# DCMotorCTRL.net
KiCad netlist of a schematic drawn in Altium Designer
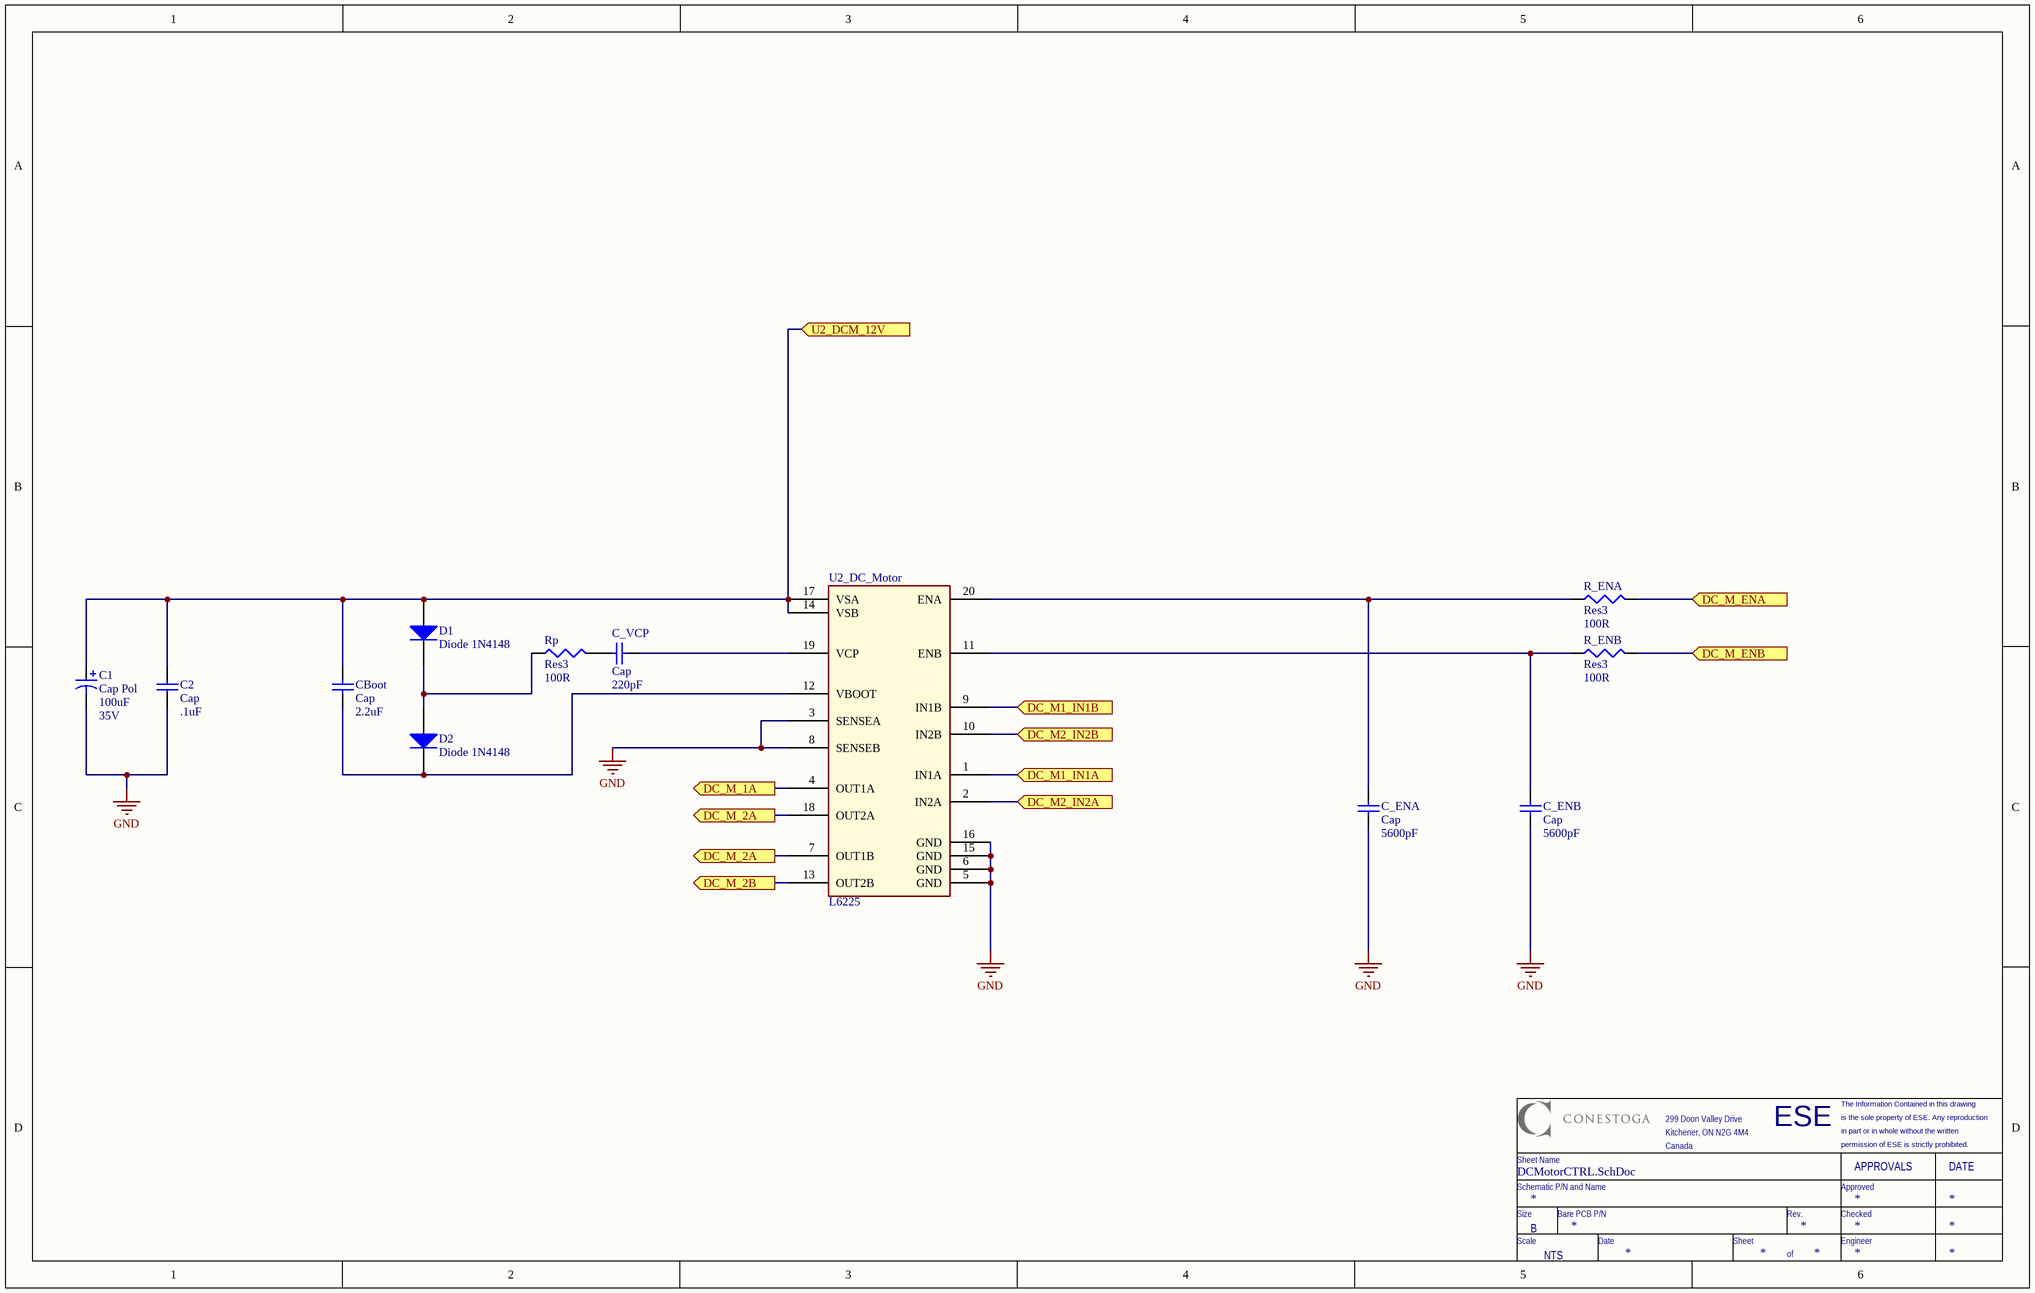
[diagram p0: DCMotorCTRL.SchDoc]

(export (version "E")
  (design (tool "Eeschema 10.0.6"))
  (components
    (comp (ref "C1")
      (value "Cap Pol")
      (footprint "CAPACITOR_6.3MM")
      (description "CAP 85C 100uF ±20% 16V WX Series Aluminum Electrolytic")
      (fields
        (field (name "ALTIUM_VALUE") "100uF")
        (field (name "VOLTAGE") "35V")
        (field (name "MPN") "UWX1C101MCL1GB")
      )
      (libsource (lib "esd_library") (part "Cap Polar-100uF-16V"))
    )
    (comp (ref "C2")
      (value "Cap")
      (footprint "CAPC2012X09M")
      (description "CAP CER .1uF 100v X7R 0805")
      (fields (field (name "ALTIUM_VALUE") ".1uF") (field (name "MPN") "C0805C104K1RACTU"))
      (libsource (lib "esd_library") (part "CAP-X7R-.1uF-100V-±10%"))
    )
    (comp (ref "CBoot")
      (value "Cap")
      (footprint "CAPC2012X09M")
      (description "CAP CER 2.2uF 16v X7R 0805")
      (fields (field (name "ALTIUM_VALUE") "2.2uF") (field (name "MPN") "C0805C225K4RACTU"))
      (libsource (lib "esd_library") (part "CAP-X7R-2.2uF-16V-±10%"))
    )
    (comp (ref "C_ENA")
      (value "Cap")
      (footprint "CAPC2012X09M")
      (description "CAP CER 5600pF 50v X7R 0805")
      (fields (field (name "ALTIUM_VALUE") "5600pF") (field (name "MPN") "C0805C562K5RACTU"))
      (libsource (lib "esd_library") (part "CAP-X7R-5600pF-50V-±10%"))
    )
    (comp (ref "C_ENB")
      (value "Cap")
      (footprint "CAPC2012X09M")
      (description "CAP CER 5600pF 50v X7R 0805")
      (fields (field (name "ALTIUM_VALUE") "5600pF") (field (name "MPN") "C0805C562K5RACTU"))
      (libsource (lib "esd_library") (part "CAP-X7R-5600pF-50V-±10%"))
    )
    (comp (ref "C_VCP")
      (value "Cap")
      (footprint "CAPC2012X09M")
      (description "CAP CER 220pF 50v COG 0805")
      (fields (field (name "ALTIUM_VALUE") "220pF") (field (name "MPN") "C0805C221J5GACTU"))
      (libsource (lib "Caps$") (part "CAP-COG-220pF-50V-±5%"))
    )
    (comp (ref "D1")
      (value "Diode 1N4148")
      (footprint "zener_sod323")
      (description "High Conductance Fast Diode")
      (libsource (lib "esd_library") (part "Diode 1N4148"))
    )
    (comp (ref "D2")
      (value "Diode 1N4148")
      (footprint "zener_sod323")
      (description "High Conductance Fast Diode")
      (libsource (lib "esd_library") (part "Diode 1N4148"))
    )
    (comp (ref "Rp")
      (value "Res3")
      (footprint "RESC2112X05M")
      (description "RES SMD 100R OHM 1% 1/8W 0805")
      (fields (field (name "ALTIUM_VALUE") "100R") (field (name "MPN") "CRCW0805100RFKEA"))
      (libsource (lib "esd_library") (part "Resistor_100R"))
    )
    (comp (ref "R_ENA")
      (value "Res3")
      (footprint "RESC2112X05M")
      (description "RES SMD 100R OHM 1% 1/8W 0805")
      (fields (field (name "ALTIUM_VALUE") "100R") (field (name "MPN") "CRCW0805100RFKEA"))
      (libsource (lib "esd_library") (part "Resistor_100R"))
    )
    (comp (ref "R_ENB")
      (value "Res3")
      (footprint "RESC2112X05M")
      (description "RES SMD 100R OHM 1% 1/8W 0805")
      (fields (field (name "ALTIUM_VALUE") "100R") (field (name "MPN") "CRCW0805100RFKEA"))
      (libsource (lib "esd_library") (part "Resistor_100R"))
    )
    (comp (ref "U2_DC_Motor")
      (value "L6225")
      (footprint "POWERSOP20")
      (description "IC MOTOR DRIVER PAR 20POWERSO")
      (fields (field (name "MPN") "L6225PDTR"))
      (libsource (lib "esd_library") (part "L6225"))
    )
  )
  (nets
    (net (code "1") (name "/DC_M1_IN1A") (class "Default")
      (node (ref "U2_DC_Motor") (pin "1") (pinfunction "IN1A_1") (pintype "passive"))
    )
    (net (code "2") (name "/DC_M1_IN1B") (class "Default")
      (node (ref "U2_DC_Motor") (pin "9") (pinfunction "IN1B_9") (pintype "passive"))
    )
    (net (code "3") (name "/DC_M2_IN2A") (class "Default")
      (node (ref "U2_DC_Motor") (pin "2") (pinfunction "IN2A_2") (pintype "passive"))
    )
    (net (code "4") (name "/DC_M2_IN2B") (class "Default")
      (node (ref "U2_DC_Motor") (pin "10") (pinfunction "IN2B_10") (pintype "passive"))
    )
    (net (code "5") (name "/DC_M_1A") (class "Default")
      (node (ref "U2_DC_Motor") (pin "4") (pinfunction "OUT1A_4") (pintype "passive"))
    )
    (net (code "6") (name "/DC_M_2A") (class "Default")
      (node (ref "U2_DC_Motor") (pin "18") (pinfunction "OUT2A_18") (pintype "passive"))
      (node (ref "U2_DC_Motor") (pin "7") (pinfunction "OUT1B_7") (pintype "passive"))
    )
    (net (code "7") (name "/DC_M_2B") (class "Default")
      (node (ref "U2_DC_Motor") (pin "13") (pinfunction "OUT2B_13") (pintype "passive"))
    )
    (net (code "8") (name "/DC_M_ENA") (class "Default")
      (node (ref "R_ENA") (pin "2") (pinfunction "2_2") (pintype "passive"))
    )
    (net (code "9") (name "/DC_M_ENB") (class "Default")
      (node (ref "R_ENB") (pin "2") (pinfunction "2_2") (pintype "passive"))
    )
    (net (code "10") (name "/U2_DCM_12V") (class "Default")
      (node (ref "C1") (pin "1") (pinfunction "1_1") (pintype "passive"))
      (node (ref "C2") (pin "2") (pinfunction "2_2") (pintype "passive"))
      (node (ref "CBoot") (pin "2") (pinfunction "2_2") (pintype "passive"))
      (node (ref "D1") (pin "A") (pinfunction "A_A") (pintype "passive"))
      (node (ref "U2_DC_Motor") (pin "14") (pinfunction "VSB_14") (pintype "power_in"))
      (node (ref "U2_DC_Motor") (pin "17") (pinfunction "VSA_17") (pintype "power_in"))
    )
    (net (code "11") (name "GND") (class "Default")
      (node (ref "C1") (pin "2") (pinfunction "2_2") (pintype "passive"))
      (node (ref "C2") (pin "1") (pinfunction "1_1") (pintype "passive"))
      (node (ref "C_ENA") (pin "1") (pinfunction "1_1") (pintype "passive"))
      (node (ref "C_ENB") (pin "1") (pinfunction "1_1") (pintype "passive"))
      (node (ref "U2_DC_Motor") (pin "15") (pinfunction "GND_15") (pintype "power_in"))
      (node (ref "U2_DC_Motor") (pin "16") (pinfunction "GND_16") (pintype "power_in"))
      (node (ref "U2_DC_Motor") (pin "3") (pinfunction "SENSEA_3") (pintype "open_collector"))
      (node (ref "U2_DC_Motor") (pin "5") (pinfunction "GND_5") (pintype "power_in"))
      (node (ref "U2_DC_Motor") (pin "6") (pinfunction "GND_6") (pintype "power_in"))
      (node (ref "U2_DC_Motor") (pin "8") (pinfunction "SENSEB_8") (pintype "power_in"))
    )
    (net (code "12") (name "Net-(C_VCP-Pad1)") (class "Default")
      (node (ref "C_VCP") (pin "1") (pinfunction "1_1") (pintype "passive"))
      (node (ref "Rp") (pin "2") (pinfunction "2_2") (pintype "passive"))
    )
    (net (code "13") (name "Net-(D1-PadK)") (class "Default")
      (node (ref "D1") (pin "K") (pinfunction "K_K") (pintype "passive"))
      (node (ref "D2") (pin "A") (pinfunction "A_A") (pintype "passive"))
      (node (ref "Rp") (pin "1") (pinfunction "1_1") (pintype "passive"))
    )
    (net (code "14") (name "Net-(U2_DC_Motor-ENA)") (class "Default")
      (node (ref "C_ENA") (pin "2") (pinfunction "2_2") (pintype "passive"))
      (node (ref "R_ENA") (pin "1") (pinfunction "1_1") (pintype "passive"))
      (node (ref "U2_DC_Motor") (pin "20") (pinfunction "ENA_20") (pintype "passive"))
    )
    (net (code "15") (name "Net-(U2_DC_Motor-ENB)") (class "Default")
      (node (ref "C_ENB") (pin "2") (pinfunction "2_2") (pintype "passive"))
      (node (ref "R_ENB") (pin "1") (pinfunction "1_1") (pintype "passive"))
      (node (ref "U2_DC_Motor") (pin "11") (pinfunction "ENB_11") (pintype "passive"))
    )
    (net (code "16") (name "Net-(U2_DC_Motor-VBOOT)") (class "Default")
      (node (ref "CBoot") (pin "1") (pinfunction "1_1") (pintype "passive"))
      (node (ref "D2") (pin "K") (pinfunction "K_K") (pintype "passive"))
      (node (ref "U2_DC_Motor") (pin "12") (pinfunction "VBOOT_12") (pintype "power_in"))
    )
    (net (code "17") (name "Net-(U2_DC_Motor-VCP)") (class "Default")
      (node (ref "C_VCP") (pin "2") (pinfunction "2_2") (pintype "passive"))
      (node (ref "U2_DC_Motor") (pin "19") (pinfunction "VCP_19") (pintype "power_in"))
    )
  )
)
